# MusicBox-BOTTOM.net
KiCad netlist of a schematic drawn in EAGLE
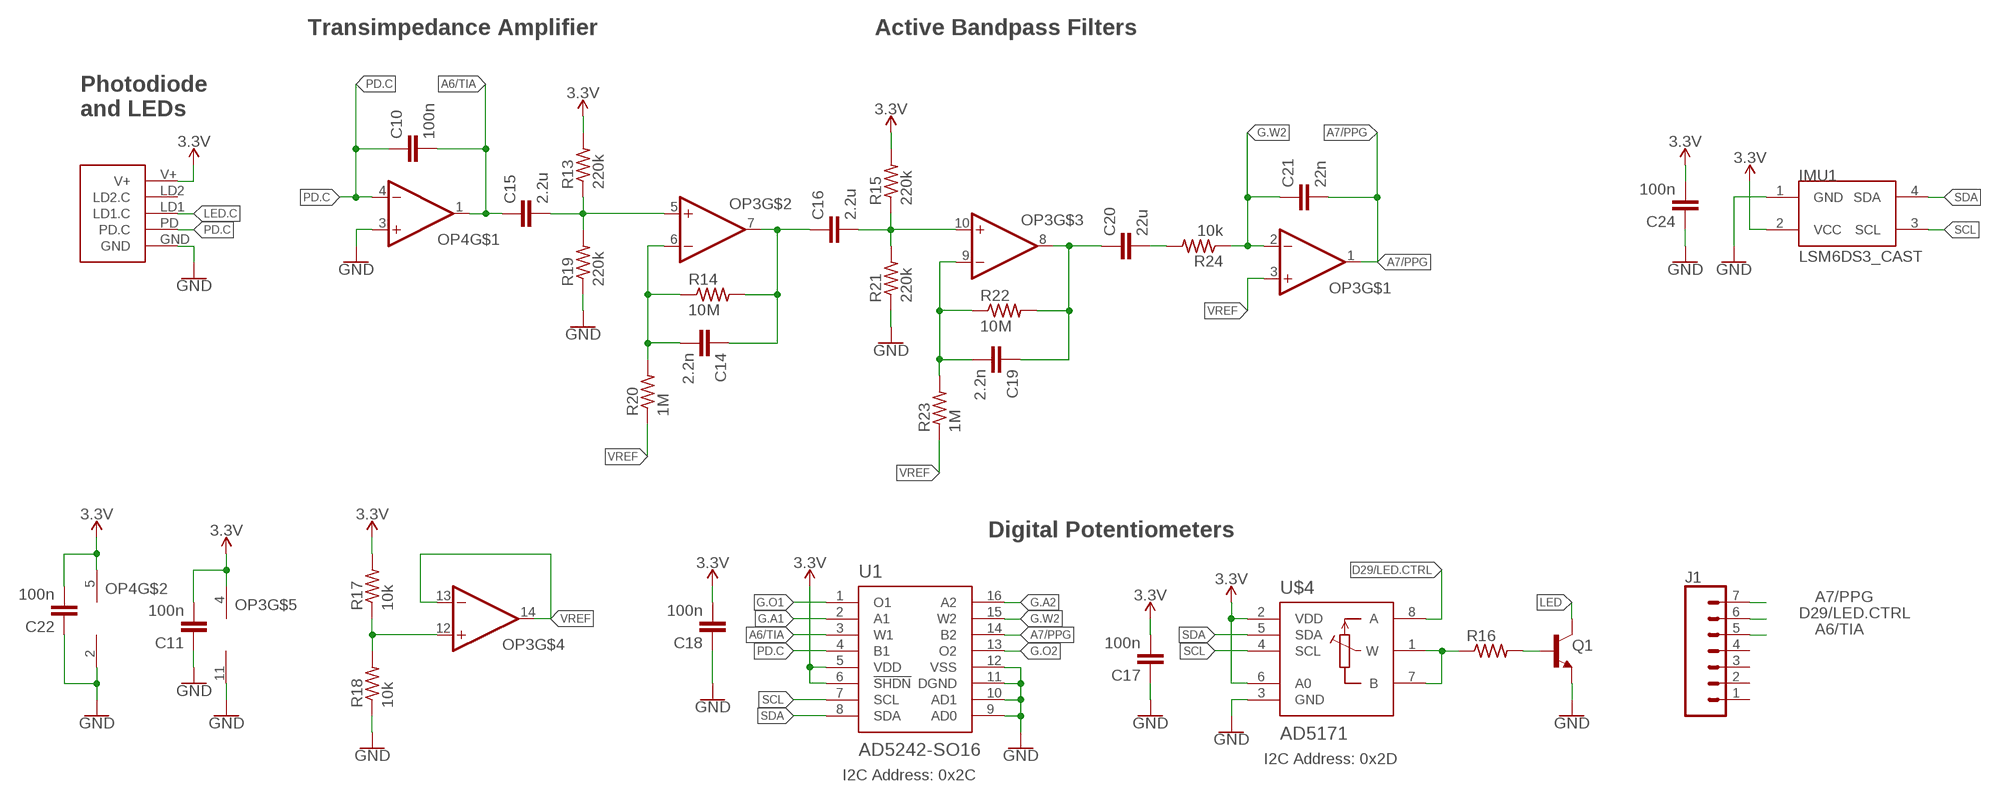
[diagram p0: schematic, sheet 1]

(export (version "E")
  (design (tool "Eeschema 10.0.6"))
  (components
    (comp (ref "C10")
      (value "100n")
      (footprint "eagle-import:C0603")
      (libsource (lib "eagle-import") (part "CAPACITOR0603"))
    )
    (comp (ref "C11")
      (value "100n")
      (footprint "eagle-import:C0603")
      (libsource (lib "eagle-import") (part "CAPACITOR0603"))
    )
    (comp (ref "C14")
      (value "2.2n")
      (footprint "eagle-import:C0603")
      (libsource (lib "eagle-import") (part "CAPACITOR0603"))
    )
    (comp (ref "C15")
      (value "2.2u")
      (footprint "eagle-import:C0603")
      (libsource (lib "eagle-import") (part "CAPACITOR0603"))
    )
    (comp (ref "C16")
      (value "2.2u")
      (footprint "eagle-import:C0603")
      (libsource (lib "eagle-import") (part "CAPACITOR0603"))
    )
    (comp (ref "C17")
      (value "100n")
      (footprint "eagle-import:C0603")
      (libsource (lib "eagle-import") (part "CAPACITOR0603"))
    )
    (comp (ref "C18")
      (value "100n")
      (footprint "eagle-import:C0603")
      (libsource (lib "eagle-import") (part "CAPACITOR0603"))
    )
    (comp (ref "C19")
      (value "2.2n")
      (footprint "eagle-import:C0603")
      (libsource (lib "eagle-import") (part "CAPACITOR0603"))
    )
    (comp (ref "C20")
      (value "22u")
      (footprint "eagle-import:C0603")
      (libsource (lib "eagle-import") (part "CAPACITOR0603"))
    )
    (comp (ref "C21")
      (value "22n")
      (footprint "eagle-import:C0603")
      (libsource (lib "eagle-import") (part "CAPACITOR0603"))
    )
    (comp (ref "C22")
      (value "100n")
      (footprint "eagle-import:C0603")
      (libsource (lib "eagle-import") (part "CAPACITOR0603"))
    )
    (comp (ref "C24")
      (value "100n")
      (footprint "eagle-import:C0603")
      (libsource (lib "eagle-import") (part "CAPACITOR0603"))
    )
    (comp (ref "IMU1")
      (value "LSM6DS3_CAST")
      (footprint "eagle-import:LSM6DS3_CAST")
      (libsource (lib "eagle-import") (part "LSM6DS3_CAST"))
    )
    (comp (ref "J1")
      (value "CONN_07")
      (footprint "eagle-import:1X07")
      (libsource (lib "eagle-import") (part "CONN_07"))
    )
    (comp (ref "OP3")
      (value "OP-QUAD-SO14")
      (footprint "eagle-import:SO14")
      (libsource (lib "eagle-import") (part "OP-QUAD-SO14"))
    )
    (comp (ref "OP4")
      (value "OP-SINGLEOT")
      (footprint "eagle-import:SOT23-5")
      (libsource (lib "eagle-import") (part "OP-SINGLEOT"))
    )
    (comp (ref "Q1")
      (value "NPN-GENERIC")
      (footprint "eagle-import:SOT23-3")
      (libsource (lib "eagle-import") (part "NPN-GENERIC"))
    )
    (comp (ref "R13")
      (value "220k")
      (footprint "eagle-import:R0603")
      (libsource (lib "eagle-import") (part "RESISTOR0603"))
    )
    (comp (ref "R14")
      (value "10M")
      (footprint "eagle-import:R0603")
      (libsource (lib "eagle-import") (part "RESISTOR0603"))
    )
    (comp (ref "R15")
      (value "220k")
      (footprint "eagle-import:R0603")
      (libsource (lib "eagle-import") (part "RESISTOR0603"))
    )
    (comp (ref "R16")
      (value "RESISTOR0603")
      (footprint "eagle-import:R0603")
      (libsource (lib "eagle-import") (part "RESISTOR0603"))
    )
    (comp (ref "R17")
      (value "10k")
      (footprint "eagle-import:R0402")
      (libsource (lib "eagle-import") (part "RESISTOR0402"))
    )
    (comp (ref "R18")
      (value "10k")
      (footprint "eagle-import:R0402")
      (libsource (lib "eagle-import") (part "RESISTOR0402"))
    )
    (comp (ref "R19")
      (value "220k")
      (footprint "eagle-import:R0603")
      (libsource (lib "eagle-import") (part "RESISTOR0603"))
    )
    (comp (ref "R20")
      (value "1M")
      (footprint "eagle-import:R0603")
      (libsource (lib "eagle-import") (part "RESISTOR0603"))
    )
    (comp (ref "R21")
      (value "220k")
      (footprint "eagle-import:R0603")
      (libsource (lib "eagle-import") (part "RESISTOR0603"))
    )
    (comp (ref "R22")
      (value "10M")
      (footprint "eagle-import:R0603")
      (libsource (lib "eagle-import") (part "RESISTOR0603"))
    )
    (comp (ref "R23")
      (value "1M")
      (footprint "eagle-import:R0603")
      (libsource (lib "eagle-import") (part "RESISTOR0603"))
    )
    (comp (ref "R24")
      (value "10k")
      (footprint "eagle-import:R0603")
      (libsource (lib "eagle-import") (part "RESISTOR0603"))
    )
    (comp (ref "U$3")
      (value "PPG.MODULE.2")
      (footprint "eagle-import:PPG.MODULE.2")
      (libsource (lib "eagle-import") (part "PPG.MODULE.2"))
    )
    (comp (ref "U$4")
      (value "AD5171")
      (footprint "eagle-import:SOT-23-8")
      (libsource (lib "eagle-import") (part "AD5171"))
    )
    (comp (ref "U1")
      (value "AD5242-SO16")
      (footprint "eagle-import:SO16")
      (libsource (lib "eagle-import") (part "AD5242-SO16"))
    )
  )
  (nets
    (net (code "1") (name "3.3V") (class "Default")
      (node (ref "C11") (pin "2") (pinfunction "2_2") (pintype "passive"))
      (node (ref "C17") (pin "2") (pinfunction "2_2") (pintype "passive"))
      (node (ref "C18") (pin "2") (pinfunction "2_2") (pintype "passive"))
      (node (ref "C22") (pin "2") (pinfunction "2_2") (pintype "passive"))
      (node (ref "C24") (pin "2") (pinfunction "2_2") (pintype "passive"))
      (node (ref "IMU1") (pin "2") (pinfunction "VCC_2") (pintype "bidirectional"))
      (node (ref "OP3") (pin "4") (pinfunction "V+_4") (pintype "power_in"))
      (node (ref "OP4") (pin "5") (pinfunction "V+_5") (pintype "power_in"))
      (node (ref "R13") (pin "2") (pinfunction "2_2") (pintype "passive"))
      (node (ref "R15") (pin "2") (pinfunction "2_2") (pintype "passive"))
      (node (ref "R17") (pin "2") (pinfunction "2_2") (pintype "passive"))
      (node (ref "U$3") (pin "V+") (pinfunction "V+_V+") (pintype "bidirectional"))
      (node (ref "U$4") (pin "2") (pinfunction "VDD_2") (pintype "bidirectional"))
      (node (ref "U$4") (pin "6") (pinfunction "A0_6") (pintype "bidirectional"))
      (node (ref "U1") (pin "5") (pinfunction "VDD_5") (pintype "bidirectional"))
      (node (ref "U1") (pin "6") (pinfunction "~{SHDN}_6") (pintype "bidirectional"))
    )
    (net (code "2") (name "A6{slash}TIA") (class "Default")
      (node (ref "C10") (pin "2") (pinfunction "2_2") (pintype "passive"))
      (node (ref "C15") (pin "1") (pinfunction "1_1") (pintype "passive"))
      (node (ref "J1") (pin "5") (pinfunction "5_5") (pintype "passive"))
      (node (ref "OP4") (pin "1") (pinfunction "OUT_1") (pintype "output"))
      (node (ref "U1") (pin "3") (pinfunction "W1_3") (pintype "bidirectional"))
    )
    (net (code "3") (name "A7{slash}PPG") (class "Default")
      (node (ref "C21") (pin "2") (pinfunction "2_2") (pintype "passive"))
      (node (ref "J1") (pin "7") (pinfunction "7_7") (pintype "passive"))
      (node (ref "OP3") (pin "1") (pinfunction "OUT_1") (pintype "output"))
      (node (ref "U1") (pin "14") (pinfunction "B2_14") (pintype "bidirectional"))
    )
    (net (code "4") (name "D29{slash}LED.CTRL") (class "Default")
      (node (ref "J1") (pin "6") (pinfunction "6_6") (pintype "passive"))
      (node (ref "U$4") (pin "8") (pinfunction "A_8") (pintype "bidirectional"))
    )
    (net (code "5") (name "G.A1") (class "Default")
      (node (ref "U1") (pin "2") (pinfunction "A1_2") (pintype "bidirectional"))
    )
    (net (code "6") (name "G.A2") (class "Default")
      (node (ref "U1") (pin "16") (pinfunction "A2_16") (pintype "bidirectional"))
    )
    (net (code "7") (name "G.O1") (class "Default")
      (node (ref "U1") (pin "1") (pinfunction "O1_1") (pintype "bidirectional"))
    )
    (net (code "8") (name "G.O2") (class "Default")
      (node (ref "U1") (pin "13") (pinfunction "O2_13") (pintype "bidirectional"))
    )
    (net (code "9") (name "G.W2") (class "Default")
      (node (ref "C21") (pin "1") (pinfunction "1_1") (pintype "passive"))
      (node (ref "OP3") (pin "2") (pinfunction "-IN_2") (pintype "input"))
      (node (ref "R24") (pin "1") (pinfunction "1_1") (pintype "passive"))
      (node (ref "U1") (pin "15") (pinfunction "W2_15") (pintype "bidirectional"))
    )
    (net (code "10") (name "GND") (class "Default")
      (node (ref "C11") (pin "1") (pinfunction "1_1") (pintype "passive"))
      (node (ref "C17") (pin "1") (pinfunction "1_1") (pintype "passive"))
      (node (ref "C18") (pin "1") (pinfunction "1_1") (pintype "passive"))
      (node (ref "C22") (pin "1") (pinfunction "1_1") (pintype "passive"))
      (node (ref "C24") (pin "1") (pinfunction "1_1") (pintype "passive"))
      (node (ref "IMU1") (pin "1") (pinfunction "GND_1") (pintype "bidirectional"))
      (node (ref "OP3") (pin "11") (pinfunction "V-_11") (pintype "power_in"))
      (node (ref "OP4") (pin "2") (pinfunction "V-_2") (pintype "power_in"))
      (node (ref "OP4") (pin "3") (pinfunction "+IN_3") (pintype "input"))
      (node (ref "Q1") (pin "2") (pinfunction "E_2") (pintype "passive"))
      (node (ref "R18") (pin "1") (pinfunction "1_1") (pintype "passive"))
      (node (ref "R19") (pin "1") (pinfunction "1_1") (pintype "passive"))
      (node (ref "R21") (pin "1") (pinfunction "1_1") (pintype "passive"))
      (node (ref "U$3") (pin "GND") (pinfunction "GND_GND") (pintype "bidirectional"))
      (node (ref "U$4") (pin "3") (pinfunction "GND_3") (pintype "bidirectional"))
      (node (ref "U1") (pin "10") (pinfunction "AD1_10") (pintype "bidirectional"))
      (node (ref "U1") (pin "11") (pinfunction "DGND_11") (pintype "bidirectional"))
      (node (ref "U1") (pin "12") (pinfunction "VSS_12") (pintype "bidirectional"))
      (node (ref "U1") (pin "9") (pinfunction "AD0_9") (pintype "bidirectional"))
    )
    (net (code "11") (name "LED") (class "Default")
      (node (ref "Q1") (pin "3") (pinfunction "C_3") (pintype "passive"))
    )
    (net (code "12") (name "LED.C") (class "Default")
      (node (ref "U$3") (pin "LD1") (pinfunction "LD1.C_LD1") (pintype "bidirectional"))
    )
    (net (code "13") (name "Net-(C20-Pad2)") (class "Default")
      (node (ref "C20") (pin "2") (pinfunction "2_2") (pintype "passive"))
      (node (ref "R24") (pin "2") (pinfunction "2_2") (pintype "passive"))
    )
    (net (code "14") (name "Net-(OP3B-+IN)") (class "Default")
      (node (ref "C15") (pin "2") (pinfunction "2_2") (pintype "passive"))
      (node (ref "OP3") (pin "5") (pinfunction "+IN_5") (pintype "input"))
      (node (ref "R13") (pin "1") (pinfunction "1_1") (pintype "passive"))
      (node (ref "R19") (pin "2") (pinfunction "2_2") (pintype "passive"))
    )
    (net (code "15") (name "Net-(OP3B--IN)") (class "Default")
      (node (ref "C14") (pin "2") (pinfunction "2_2") (pintype "passive"))
      (node (ref "OP3") (pin "6") (pinfunction "-IN_6") (pintype "input"))
      (node (ref "R14") (pin "1") (pinfunction "1_1") (pintype "passive"))
      (node (ref "R20") (pin "2") (pinfunction "2_2") (pintype "passive"))
    )
    (net (code "16") (name "Net-(OP3B-OUT)") (class "Default")
      (node (ref "C14") (pin "1") (pinfunction "1_1") (pintype "passive"))
      (node (ref "C16") (pin "1") (pinfunction "1_1") (pintype "passive"))
      (node (ref "OP3") (pin "7") (pinfunction "OUT_7") (pintype "output"))
      (node (ref "R14") (pin "2") (pinfunction "2_2") (pintype "passive"))
    )
    (net (code "17") (name "Net-(OP3C-+IN)") (class "Default")
      (node (ref "C16") (pin "2") (pinfunction "2_2") (pintype "passive"))
      (node (ref "OP3") (pin "10") (pinfunction "+IN_10") (pintype "input"))
      (node (ref "R15") (pin "1") (pinfunction "1_1") (pintype "passive"))
      (node (ref "R21") (pin "2") (pinfunction "2_2") (pintype "passive"))
    )
    (net (code "18") (name "Net-(OP3C--IN)") (class "Default")
      (node (ref "C19") (pin "2") (pinfunction "2_2") (pintype "passive"))
      (node (ref "OP3") (pin "9") (pinfunction "-IN_9") (pintype "input"))
      (node (ref "R22") (pin "1") (pinfunction "1_1") (pintype "passive"))
      (node (ref "R23") (pin "2") (pinfunction "2_2") (pintype "passive"))
    )
    (net (code "19") (name "Net-(OP3C-OUT)") (class "Default")
      (node (ref "C19") (pin "1") (pinfunction "1_1") (pintype "passive"))
      (node (ref "C20") (pin "1") (pinfunction "1_1") (pintype "passive"))
      (node (ref "OP3") (pin "8") (pinfunction "OUT_8") (pintype "output"))
      (node (ref "R22") (pin "2") (pinfunction "2_2") (pintype "passive"))
    )
    (net (code "20") (name "Net-(OP3D-+IN)") (class "Default")
      (node (ref "OP3") (pin "12") (pinfunction "+IN_12") (pintype "input"))
      (node (ref "R17") (pin "1") (pinfunction "1_1") (pintype "passive"))
      (node (ref "R18") (pin "2") (pinfunction "2_2") (pintype "passive"))
    )
    (net (code "21") (name "Net-(Q1-B)") (class "Default")
      (node (ref "Q1") (pin "1") (pinfunction "B_1") (pintype "passive"))
      (node (ref "R16") (pin "2") (pinfunction "2_2") (pintype "passive"))
    )
    (net (code "22") (name "Net-(U$4-B)") (class "Default")
      (node (ref "R16") (pin "1") (pinfunction "1_1") (pintype "passive"))
      (node (ref "U$4") (pin "1") (pinfunction "W_1") (pintype "bidirectional"))
      (node (ref "U$4") (pin "7") (pinfunction "B_7") (pintype "bidirectional"))
    )
    (net (code "23") (name "PD.C") (class "Default")
      (node (ref "C10") (pin "1") (pinfunction "1_1") (pintype "passive"))
      (node (ref "OP4") (pin "4") (pinfunction "-IN_4") (pintype "input"))
      (node (ref "U$3") (pin "PD") (pinfunction "PD.C_PD") (pintype "bidirectional"))
      (node (ref "U1") (pin "4") (pinfunction "B1_4") (pintype "bidirectional"))
    )
    (net (code "24") (name "SCL") (class "Default")
      (node (ref "IMU1") (pin "3") (pinfunction "SCL_3") (pintype "bidirectional"))
      (node (ref "U$4") (pin "4") (pinfunction "SCL_4") (pintype "bidirectional"))
      (node (ref "U1") (pin "7") (pinfunction "SCL_7") (pintype "bidirectional"))
    )
    (net (code "25") (name "SDA") (class "Default")
      (node (ref "IMU1") (pin "4") (pinfunction "SDA_4") (pintype "bidirectional"))
      (node (ref "U$4") (pin "5") (pinfunction "SDA_5") (pintype "bidirectional"))
      (node (ref "U1") (pin "8") (pinfunction "SDA_8") (pintype "bidirectional"))
    )
    (net (code "26") (name "VREF") (class "Default")
      (node (ref "OP3") (pin "13") (pinfunction "-IN_13") (pintype "input"))
      (node (ref "OP3") (pin "14") (pinfunction "OUT_14") (pintype "output"))
      (node (ref "OP3") (pin "3") (pinfunction "+IN_3") (pintype "input"))
      (node (ref "R20") (pin "1") (pinfunction "1_1") (pintype "passive"))
      (node (ref "R23") (pin "1") (pinfunction "1_1") (pintype "passive"))
    )
    (net (code "27") (name "unconnected-(J1-Pad1)") (class "Default")
      (node (ref "J1") (pin "1") (pinfunction "1_1") (pintype "passive"))
    )
    (net (code "28") (name "unconnected-(J1-Pad2)") (class "Default")
      (node (ref "J1") (pin "2") (pinfunction "2_2") (pintype "passive"))
    )
    (net (code "29") (name "unconnected-(J1-Pad3)") (class "Default")
      (node (ref "J1") (pin "3") (pinfunction "3_3") (pintype "passive"))
    )
    (net (code "30") (name "unconnected-(J1-Pad4)") (class "Default")
      (node (ref "J1") (pin "4") (pinfunction "4_4") (pintype "passive"))
    )
    (net (code "31") (name "unconnected-(U$3-LD2.C-PadLD2)") (class "Default")
      (node (ref "U$3") (pin "LD2") (pinfunction "LD2.C_LD2") (pintype "bidirectional"))
    )
  )
)
